# 2014_ConnecteurChargeur.net
KiCad netlist of a schematic drawn in Altium Designer
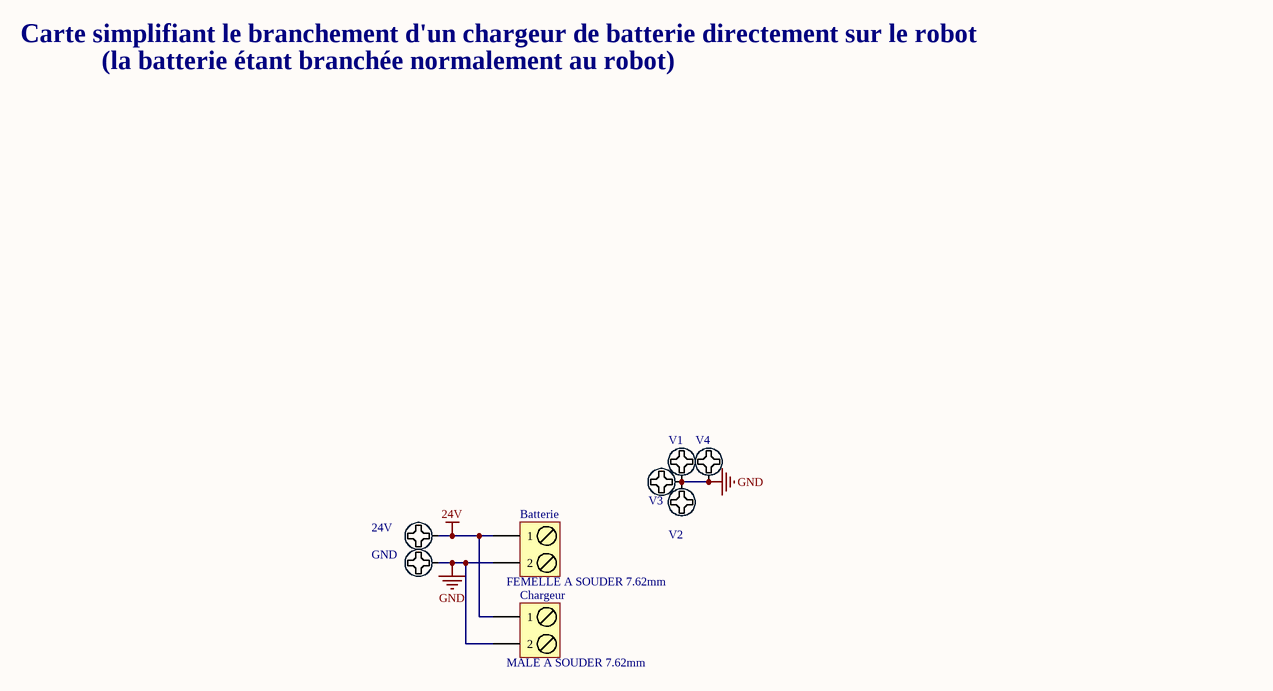
[diagram p0: 2014_ConnecteurChargeur.SchDoc]

(export (version "E")
  (design (tool "Eeschema 10.0.6"))
  (components
    (comp (ref "24V")
      (value "Pad_M3")
      (footprint "M3x6mm_8 vias")
      (description "Vis M3 X 6mm _TORX_Tête 6mm")
      (fields (field (name "PUBLISHER") "Damien Guitton"))
      (libsource (lib "_ROBOT") (part "Vis M3 X 6mm _TORX_Tête 6mm"))
    )
    (comp (ref "Batterie")
      (value "FEMELLE A SOUDER 7.62mm")
      (footprint "BORNIER2_FEM_COUDE")
      (description "Terminal blocks, 2 pins, pitch=5mm")
      (libsource (lib "Connecteur") (part "BORNIER2"))
    )
    (comp (ref "Chargeur")
      (value "MALE A SOUDER 7.62mm")
      (footprint "BORNIER2_FEM_COUDE")
      (description "Terminal blocks, 2 pins, pitch=5mm")
      (libsource (lib "Connecteur") (part "BORNIER2"))
    )
    (comp (ref "GND")
      (value "Pad_M3")
      (footprint "M3x6mm_8 vias")
      (description "Vis M3 X 6mm _TORX_Tête 6mm")
      (fields (field (name "PUBLISHER") "Damien Guitton"))
      (libsource (lib "_ROBOT") (part "Vis M3 X 6mm _TORX_Tête 6mm"))
    )
    (comp (ref "V1")
      (value "Pad_M3")
      (footprint "M3x6mm_8 vias")
      (description "Vis M3 X 6mm _TORX_Tête 6mm")
      (fields (field (name "PUBLISHER") "Damien Guitton"))
      (libsource (lib "_ROBOT") (part "Vis M3 X 6mm _TORX_Tête 6mm"))
    )
    (comp (ref "V2")
      (value "Pad_M3")
      (footprint "M3x6mm_8 vias")
      (description "Vis M3 X 6mm _TORX_Tête 6mm")
      (fields (field (name "PUBLISHER") "Damien Guitton"))
      (libsource (lib "_ROBOT") (part "Vis M3 X 6mm _TORX_Tête 6mm"))
    )
    (comp (ref "V3")
      (value "Pad_M3")
      (footprint "DG_Mecanique_Visserie:M3x6mm_8 vias")
      (description "Vis M3 X 6mm _TORX_Tête 6mm")
      (fields (field (name "PUBLISHER") "Damien Guitton"))
      (libsource (lib "_ROBOT") (part "Vis M3 X 6mm _TORX_Tête 6mm"))
    )
    (comp (ref "V4")
      (value "Pad_M3")
      (footprint "M3x6mm_8 vias")
      (description "Vis M3 X 6mm _TORX_Tête 6mm")
      (fields (field (name "PUBLISHER") "Damien Guitton"))
      (libsource (lib "_ROBOT") (part "Vis M3 X 6mm _TORX_Tête 6mm"))
    )
  )
  (nets
    (net (code "1") (name "24V") (class "Default")
      (node (ref "24V") (pin "1") (pinfunction "1_1") (pintype "passive"))
      (node (ref "Batterie") (pin "1") (pinfunction "1_1") (pintype "passive"))
      (node (ref "Chargeur") (pin "1") (pinfunction "1_1") (pintype "passive"))
    )
    (net (code "2") (name "GND") (class "Default")
      (node (ref "Batterie") (pin "2") (pinfunction "2_2") (pintype "passive"))
      (node (ref "Chargeur") (pin "2") (pinfunction "2_2") (pintype "passive"))
      (node (ref "GND") (pin "1") (pinfunction "1_1") (pintype "passive"))
      (node (ref "V1") (pin "1") (pinfunction "1_1") (pintype "passive"))
      (node (ref "V2") (pin "1") (pinfunction "1_1") (pintype "passive"))
      (node (ref "V3") (pin "1") (pinfunction "1_1") (pintype "passive"))
      (node (ref "V4") (pin "1") (pinfunction "1_1") (pintype "passive"))
    )
  )
)
